# MicroViewUSB.net
KiCad netlist of a schematic drawn in EAGLE
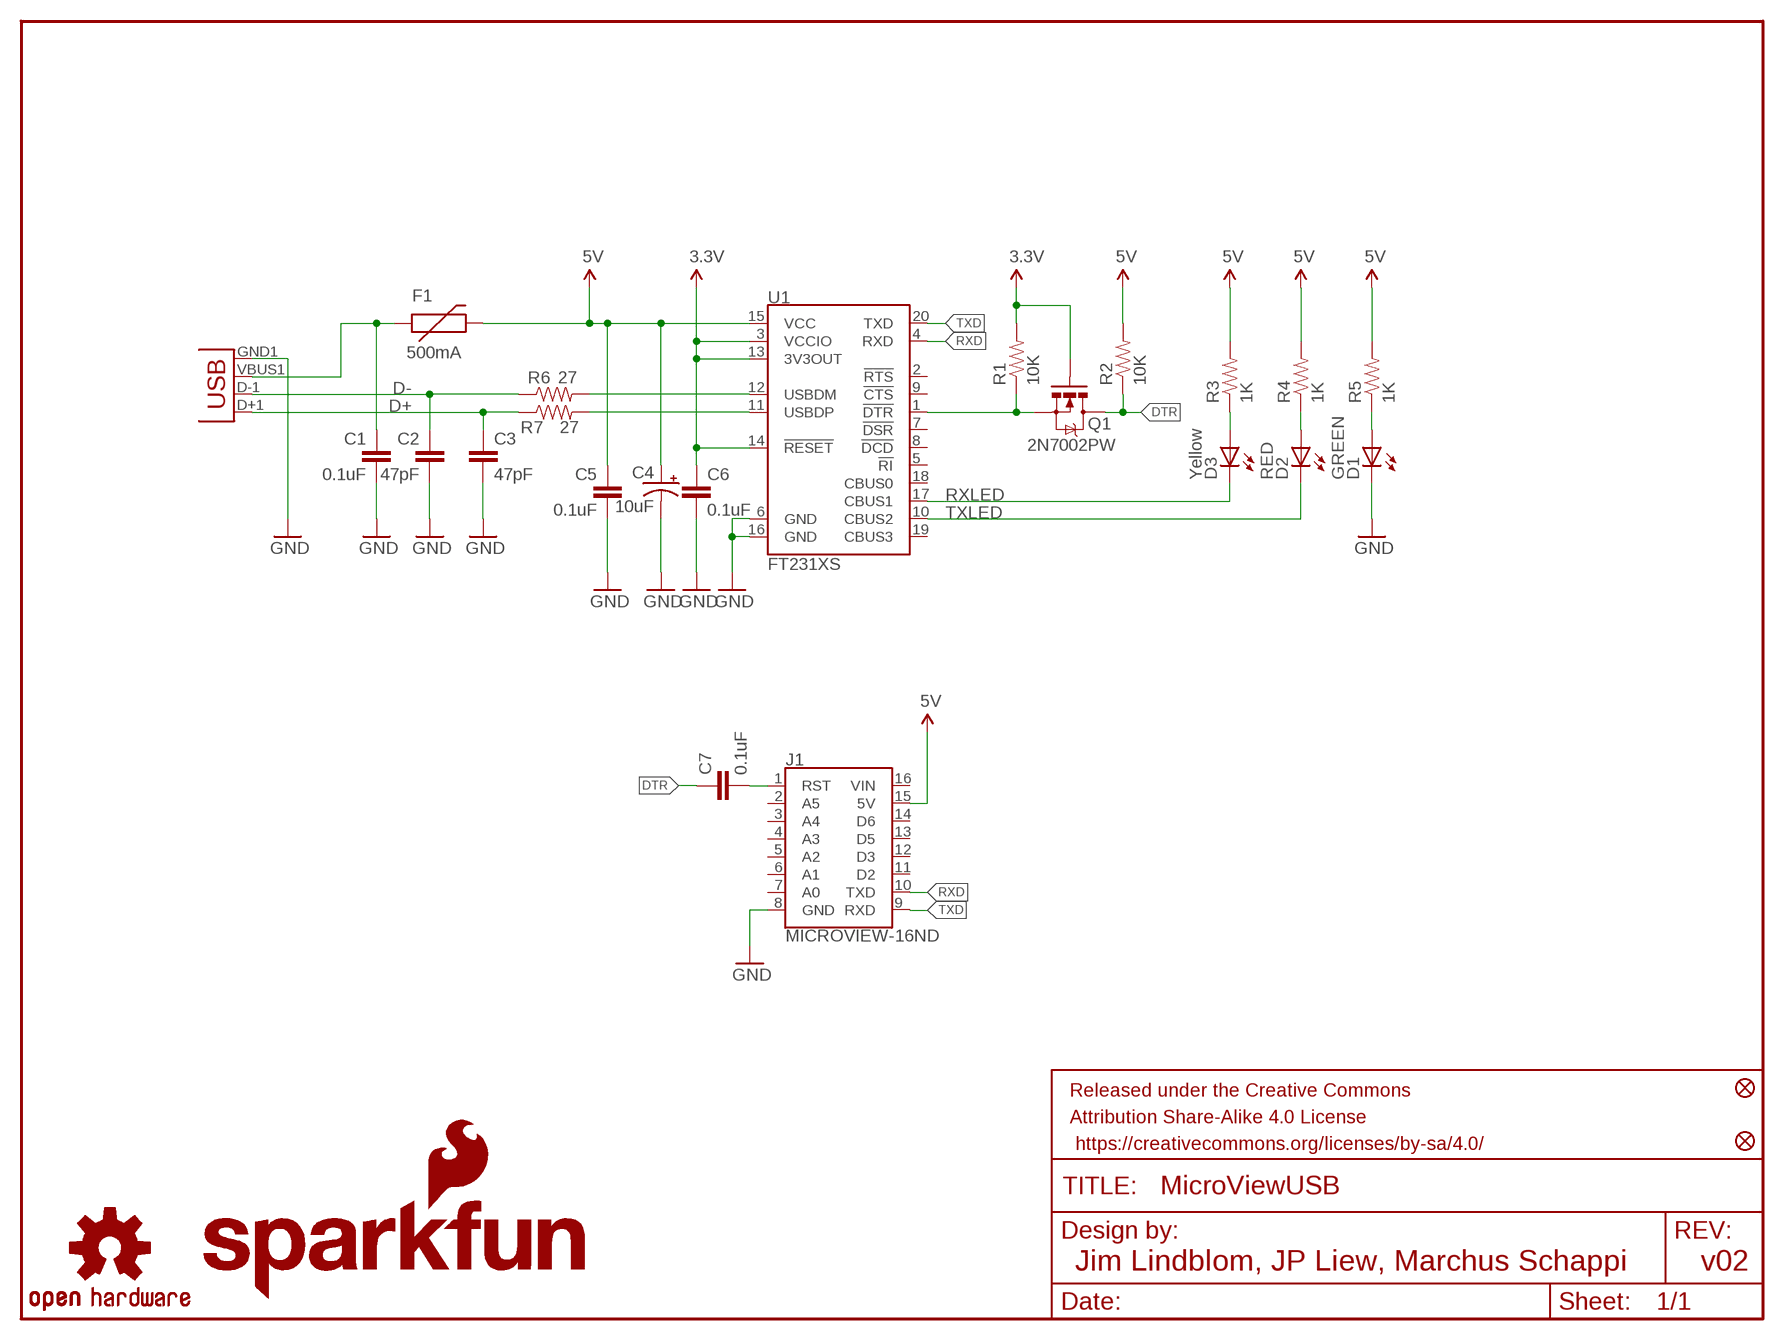
[diagram p0: schematic, sheet 1]

(export (version "E")
  (design (tool "Eeschema 10.0.6"))
  (components
    (comp (ref "C1")
      (value "0.1uF")
      (footprint "eagle-import:0603-CAP")
      (libsource (lib "eagle-import") (part "0.1UF-25V(+80/-20%)(0603)"))
    )
    (comp (ref "C2")
      (value "47pF")
      (footprint "eagle-import:0603-CAP")
      (libsource (lib "eagle-import") (part "47PF-50V-5%(0603)"))
    )
    (comp (ref "C3")
      (value "47pF")
      (footprint "eagle-import:0603-CAP")
      (libsource (lib "eagle-import") (part "47PF-50V-5%(0603)"))
    )
    (comp (ref "C4")
      (value "10uF")
      (footprint "eagle-import:EIA3216")
      (libsource (lib "eagle-import") (part "10UF-16V-10%(TANT)"))
    )
    (comp (ref "C5")
      (value "0.1uF")
      (footprint "eagle-import:0603-CAP")
      (libsource (lib "eagle-import") (part "0.1UF-25V(+80/-20%)(0603)"))
    )
    (comp (ref "C6")
      (value "0.1uF")
      (footprint "eagle-import:0603-CAP")
      (libsource (lib "eagle-import") (part "0.1UF-25V(+80/-20%)(0603)"))
    )
    (comp (ref "C7")
      (value "0.1uF")
      (footprint "eagle-import:0603-CAP")
      (libsource (lib "eagle-import") (part "0.1UF-25V(+80/-20%)(0603)"))
    )
    (comp (ref "D1")
      (value "GREEN")
      (footprint "eagle-import:LED-1206")
      (libsource (lib "eagle-import") (part "LED-GREENLARGE"))
    )
    (comp (ref "D2")
      (value "RED")
      (footprint "eagle-import:LED-1206")
      (libsource (lib "eagle-import") (part "LED-RED1206"))
    )
    (comp (ref "D3")
      (value "Yellow")
      (footprint "eagle-import:LED-1206")
      (libsource (lib "eagle-import") (part "LED-YELLOWLILYPAD"))
    )
    (comp (ref "F1")
      (value "500mA")
      (footprint "eagle-import:PTC-1206-WIDE")
      (libsource (lib "eagle-import") (part "PTCSMD-W"))
    )
    (comp (ref "FID1")
      (value "FIDUCIAL1X2")
      (footprint "eagle-import:FIDUCIAL-1X2")
      (libsource (lib "eagle-import") (part "FIDUCIAL1X2"))
    )
    (comp (ref "FID2")
      (value "FIDUCIAL1X2")
      (footprint "eagle-import:FIDUCIAL-1X2")
      (libsource (lib "eagle-import") (part "FIDUCIAL1X2"))
    )
    (comp (ref "FRAME1")
      (value "FRAME-LETTER")
      (footprint "eagle-import:CREATIVE_COMMONS")
      (libsource (lib "eagle-import") (part "FRAME-LETTER"))
    )
    (comp (ref "J1")
      (value "MICROVIEW-16ND")
      (footprint "eagle-import:MV-DIP16-NODIMENSION")
      (libsource (lib "eagle-import") (part "MICROVIEW-16ND"))
    )
    (comp (ref "JP1")
      (value "USBA-SMD-MALE")
      (footprint "eagle-import:USB-A-SMT-MALE")
      (libsource (lib "eagle-import") (part "USBA-SMD-MALE"))
    )
    (comp (ref "LOGO1")
      (value "SFE_LOGO_FLAME.1_INCH")
      (footprint "eagle-import:SFE_LOGO_FLAME_.1")
      (libsource (lib "eagle-import") (part "SFE_LOGO_FLAME.1_INCH"))
    )
    (comp (ref "LOGO2")
      (value "OSHW-LOGOS")
      (footprint "eagle-import:OSHW-LOGO-S")
      (libsource (lib "eagle-import") (part "OSHW-LOGOS"))
    )
    (comp (ref "LOGO3")
      (value "SFE_LOGO_NAME_FLAME.1_INCH")
      (footprint "eagle-import:SFE_LOGO_NAME_FLAME_.1")
      (libsource (lib "eagle-import") (part "SFE_LOGO_NAME_FLAME.1_INCH"))
    )
    (comp (ref "Q1")
      (value "2N7002PW")
      (footprint "eagle-import:SOT323")
      (libsource (lib "eagle-import") (part "MOSFET-NCHANNEL2N7002PW"))
    )
    (comp (ref "R1")
      (value "10K")
      (footprint "eagle-import:0603-RES")
      (libsource (lib "eagle-import") (part "10KOHM1/10W1%(0603)0603"))
    )
    (comp (ref "R2")
      (value "10K")
      (footprint "eagle-import:0603-RES")
      (libsource (lib "eagle-import") (part "10KOHM1/10W1%(0603)0603"))
    )
    (comp (ref "R3")
      (value "1K")
      (footprint "eagle-import:0603-RES")
      (libsource (lib "eagle-import") (part "1KOHM1/10W1%(0603)"))
    )
    (comp (ref "R4")
      (value "1K")
      (footprint "eagle-import:0603-RES")
      (libsource (lib "eagle-import") (part "1KOHM1/10W1%(0603)"))
    )
    (comp (ref "R5")
      (value "1K")
      (footprint "eagle-import:0603-RES")
      (libsource (lib "eagle-import") (part "1KOHM1/10W1%(0603)"))
    )
    (comp (ref "R6")
      (value "27")
      (footprint "eagle-import:0603-RES")
      (libsource (lib "eagle-import") (part "RESISTOR0603-RES"))
    )
    (comp (ref "R7")
      (value "27")
      (footprint "eagle-import:0603-RES")
      (libsource (lib "eagle-import") (part "RESISTOR0603-RES"))
    )
    (comp (ref "U1")
      (value "FT231XS")
      (footprint "eagle-import:SSOP20_L")
      (libsource (lib "eagle-import") (part "FT231XS"))
    )
  )
  (nets
    (net (code "1") (name "/D+") (class "Default")
      (node (ref "C3") (pin "1") (pinfunction "1_1") (pintype "passive"))
      (node (ref "JP1") (pin "D+1") (pinfunction "D+_D+1") (pintype "bidirectional"))
      (node (ref "R7") (pin "1") (pinfunction "1_1") (pintype "passive"))
    )
    (net (code "2") (name "/D-") (class "Default")
      (node (ref "C2") (pin "1") (pinfunction "1_1") (pintype "passive"))
      (node (ref "JP1") (pin "D-1") (pinfunction "D-_D-1") (pintype "bidirectional"))
      (node (ref "R6") (pin "1") (pinfunction "1_1") (pintype "passive"))
    )
    (net (code "3") (name "/RXLED") (class "Default")
      (node (ref "D3") (pin "C") (pinfunction "C_C") (pintype "passive"))
      (node (ref "U1") (pin "17") (pinfunction "CBUS1_17") (pintype "bidirectional"))
    )
    (net (code "4") (name "/TXLED") (class "Default")
      (node (ref "D2") (pin "C") (pinfunction "C_C") (pintype "passive"))
      (node (ref "U1") (pin "10") (pinfunction "CBUS2_10") (pintype "bidirectional"))
    )
    (net (code "5") (name "3.3V") (class "Default")
      (node (ref "C6") (pin "1") (pinfunction "1_1") (pintype "passive"))
      (node (ref "Q1") (pin "1") (pinfunction "G_1") (pintype "passive"))
      (node (ref "R1") (pin "2") (pinfunction "2_2") (pintype "passive"))
      (node (ref "U1") (pin "13") (pinfunction "3V3OUT_13") (pintype "bidirectional"))
      (node (ref "U1") (pin "14") (pinfunction "~{RESET}_14") (pintype "bidirectional"))
      (node (ref "U1") (pin "3") (pinfunction "VCCIO_3") (pintype "bidirectional"))
    )
    (net (code "6") (name "5V") (class "Default")
      (node (ref "C4") (pin "A") (pinfunction "+_A") (pintype "passive"))
      (node (ref "C5") (pin "1") (pinfunction "1_1") (pintype "passive"))
      (node (ref "F1") (pin "2") (pinfunction "2_2") (pintype "bidirectional"))
      (node (ref "J1") (pin "15") (pinfunction "5V_15") (pintype "output"))
      (node (ref "R2") (pin "2") (pinfunction "2_2") (pintype "passive"))
      (node (ref "R3") (pin "2") (pinfunction "2_2") (pintype "passive"))
      (node (ref "R4") (pin "2") (pinfunction "2_2") (pintype "passive"))
      (node (ref "R5") (pin "2") (pinfunction "2_2") (pintype "passive"))
      (node (ref "U1") (pin "15") (pinfunction "VCC_15") (pintype "bidirectional"))
    )
    (net (code "7") (name "DTR") (class "Default")
      (node (ref "C7") (pin "1") (pinfunction "1_1") (pintype "passive"))
      (node (ref "Q1") (pin "3") (pinfunction "D_3") (pintype "passive"))
      (node (ref "R2") (pin "1") (pinfunction "1_1") (pintype "passive"))
    )
    (net (code "8") (name "GND") (class "Default")
      (node (ref "C1") (pin "2") (pinfunction "2_2") (pintype "passive"))
      (node (ref "C2") (pin "2") (pinfunction "2_2") (pintype "passive"))
      (node (ref "C3") (pin "2") (pinfunction "2_2") (pintype "passive"))
      (node (ref "C4") (pin "C") (pinfunction "-_C") (pintype "passive"))
      (node (ref "C5") (pin "2") (pinfunction "2_2") (pintype "passive"))
      (node (ref "C6") (pin "2") (pinfunction "2_2") (pintype "passive"))
      (node (ref "D1") (pin "C") (pinfunction "C_C") (pintype "passive"))
      (node (ref "J1") (pin "8") (pinfunction "GND_8") (pintype "output"))
      (node (ref "JP1") (pin "GND1") (pinfunction "GND_GND1") (pintype "bidirectional"))
      (node (ref "U1") (pin "16") (pinfunction "GND_16") (pintype "bidirectional"))
      (node (ref "U1") (pin "6") (pinfunction "GND_6") (pintype "bidirectional"))
    )
    (net (code "9") (name "Net-(D1-PadA)") (class "Default")
      (node (ref "D1") (pin "A") (pinfunction "A_A") (pintype "passive"))
      (node (ref "R5") (pin "1") (pinfunction "1_1") (pintype "passive"))
    )
    (net (code "10") (name "Net-(D2-PadA)") (class "Default")
      (node (ref "D2") (pin "A") (pinfunction "A_A") (pintype "passive"))
      (node (ref "R4") (pin "1") (pinfunction "1_1") (pintype "passive"))
    )
    (net (code "11") (name "Net-(D3-PadA)") (class "Default")
      (node (ref "D3") (pin "A") (pinfunction "A_A") (pintype "passive"))
      (node (ref "R3") (pin "1") (pinfunction "1_1") (pintype "passive"))
    )
    (net (code "12") (name "Net-(J1-RST)") (class "Default")
      (node (ref "C7") (pin "2") (pinfunction "2_2") (pintype "passive"))
      (node (ref "J1") (pin "1") (pinfunction "RST_1") (pintype "output"))
    )
    (net (code "13") (name "Net-(JP1-VBUS)") (class "Default")
      (node (ref "C1") (pin "1") (pinfunction "1_1") (pintype "passive"))
      (node (ref "F1") (pin "1") (pinfunction "1_1") (pintype "bidirectional"))
      (node (ref "JP1") (pin "VBUS1") (pinfunction "VBUS_VBUS1") (pintype "bidirectional"))
    )
    (net (code "14") (name "Net-(Q1-S)") (class "Default")
      (node (ref "Q1") (pin "2") (pinfunction "S_2") (pintype "passive"))
      (node (ref "R1") (pin "1") (pinfunction "1_1") (pintype "passive"))
      (node (ref "U1") (pin "1") (pinfunction "~{DTR}_1") (pintype "bidirectional"))
    )
    (net (code "15") (name "Net-(U1-USBDM)") (class "Default")
      (node (ref "R6") (pin "2") (pinfunction "2_2") (pintype "passive"))
      (node (ref "U1") (pin "12") (pinfunction "USBDM_12") (pintype "bidirectional"))
    )
    (net (code "16") (name "Net-(U1-USBDP)") (class "Default")
      (node (ref "R7") (pin "2") (pinfunction "2_2") (pintype "passive"))
      (node (ref "U1") (pin "11") (pinfunction "USBDP_11") (pintype "bidirectional"))
    )
    (net (code "17") (name "RXD") (class "Default")
      (node (ref "J1") (pin "10") (pinfunction "TXD_10") (pintype "output"))
      (node (ref "U1") (pin "4") (pinfunction "RXD_4") (pintype "bidirectional"))
    )
    (net (code "18") (name "TXD") (class "Default")
      (node (ref "J1") (pin "9") (pinfunction "RXD_9") (pintype "output"))
      (node (ref "U1") (pin "20") (pinfunction "TXD_20") (pintype "bidirectional"))
    )
    (net (code "19") (name "unconnected-(J1-A0-Pad7)") (class "Default")
      (node (ref "J1") (pin "7") (pinfunction "A0_7") (pintype "output"))
    )
    (net (code "20") (name "unconnected-(J1-A1-Pad6)") (class "Default")
      (node (ref "J1") (pin "6") (pinfunction "A1_6") (pintype "output"))
    )
    (net (code "21") (name "unconnected-(J1-A2-Pad5)") (class "Default")
      (node (ref "J1") (pin "5") (pinfunction "A2_5") (pintype "output"))
    )
    (net (code "22") (name "unconnected-(J1-A3-Pad4)") (class "Default")
      (node (ref "J1") (pin "4") (pinfunction "A3_4") (pintype "output"))
    )
    (net (code "23") (name "unconnected-(J1-A4-Pad3)") (class "Default")
      (node (ref "J1") (pin "3") (pinfunction "A4_3") (pintype "output"))
    )
    (net (code "24") (name "unconnected-(J1-A5-Pad2)") (class "Default")
      (node (ref "J1") (pin "2") (pinfunction "A5_2") (pintype "output"))
    )
    (net (code "25") (name "unconnected-(J1-D2-Pad11)") (class "Default")
      (node (ref "J1") (pin "11") (pinfunction "D2_11") (pintype "output"))
    )
    (net (code "26") (name "unconnected-(J1-D3-Pad12)") (class "Default")
      (node (ref "J1") (pin "12") (pinfunction "D3_12") (pintype "output"))
    )
    (net (code "27") (name "unconnected-(J1-D5-Pad13)") (class "Default")
      (node (ref "J1") (pin "13") (pinfunction "D5_13") (pintype "output"))
    )
    (net (code "28") (name "unconnected-(J1-D6-Pad14)") (class "Default")
      (node (ref "J1") (pin "14") (pinfunction "D6_14") (pintype "output"))
    )
    (net (code "29") (name "unconnected-(J1-VIN-Pad16)") (class "Default")
      (node (ref "J1") (pin "16") (pinfunction "VIN_16") (pintype "output"))
    )
    (net (code "30") (name "unconnected-(U1-CBUS0-Pad18)") (class "Default")
      (node (ref "U1") (pin "18") (pinfunction "CBUS0_18") (pintype "bidirectional"))
    )
    (net (code "31") (name "unconnected-(U1-CBUS3-Pad19)") (class "Default")
      (node (ref "U1") (pin "19") (pinfunction "CBUS3_19") (pintype "bidirectional"))
    )
    (net (code "32") (name "unconnected-(U1-~{CTS}-Pad9)") (class "Default")
      (node (ref "U1") (pin "9") (pinfunction "~{CTS}_9") (pintype "bidirectional"))
    )
    (net (code "33") (name "unconnected-(U1-~{DCD}-Pad8)") (class "Default")
      (node (ref "U1") (pin "8") (pinfunction "~{DCD}_8") (pintype "bidirectional"))
    )
    (net (code "34") (name "unconnected-(U1-~{DSR}-Pad7)") (class "Default")
      (node (ref "U1") (pin "7") (pinfunction "~{DSR}_7") (pintype "bidirectional"))
    )
    (net (code "35") (name "unconnected-(U1-~{RI}-Pad5)") (class "Default")
      (node (ref "U1") (pin "5") (pinfunction "~{RI}_5") (pintype "bidirectional"))
    )
    (net (code "36") (name "unconnected-(U1-~{RTS}-Pad2)") (class "Default")
      (node (ref "U1") (pin "2") (pinfunction "~{RTS}_2") (pintype "bidirectional"))
    )
  )
)
